# single_asic_miner.net
KiCad netlist of a schematic drawn in EAGLE
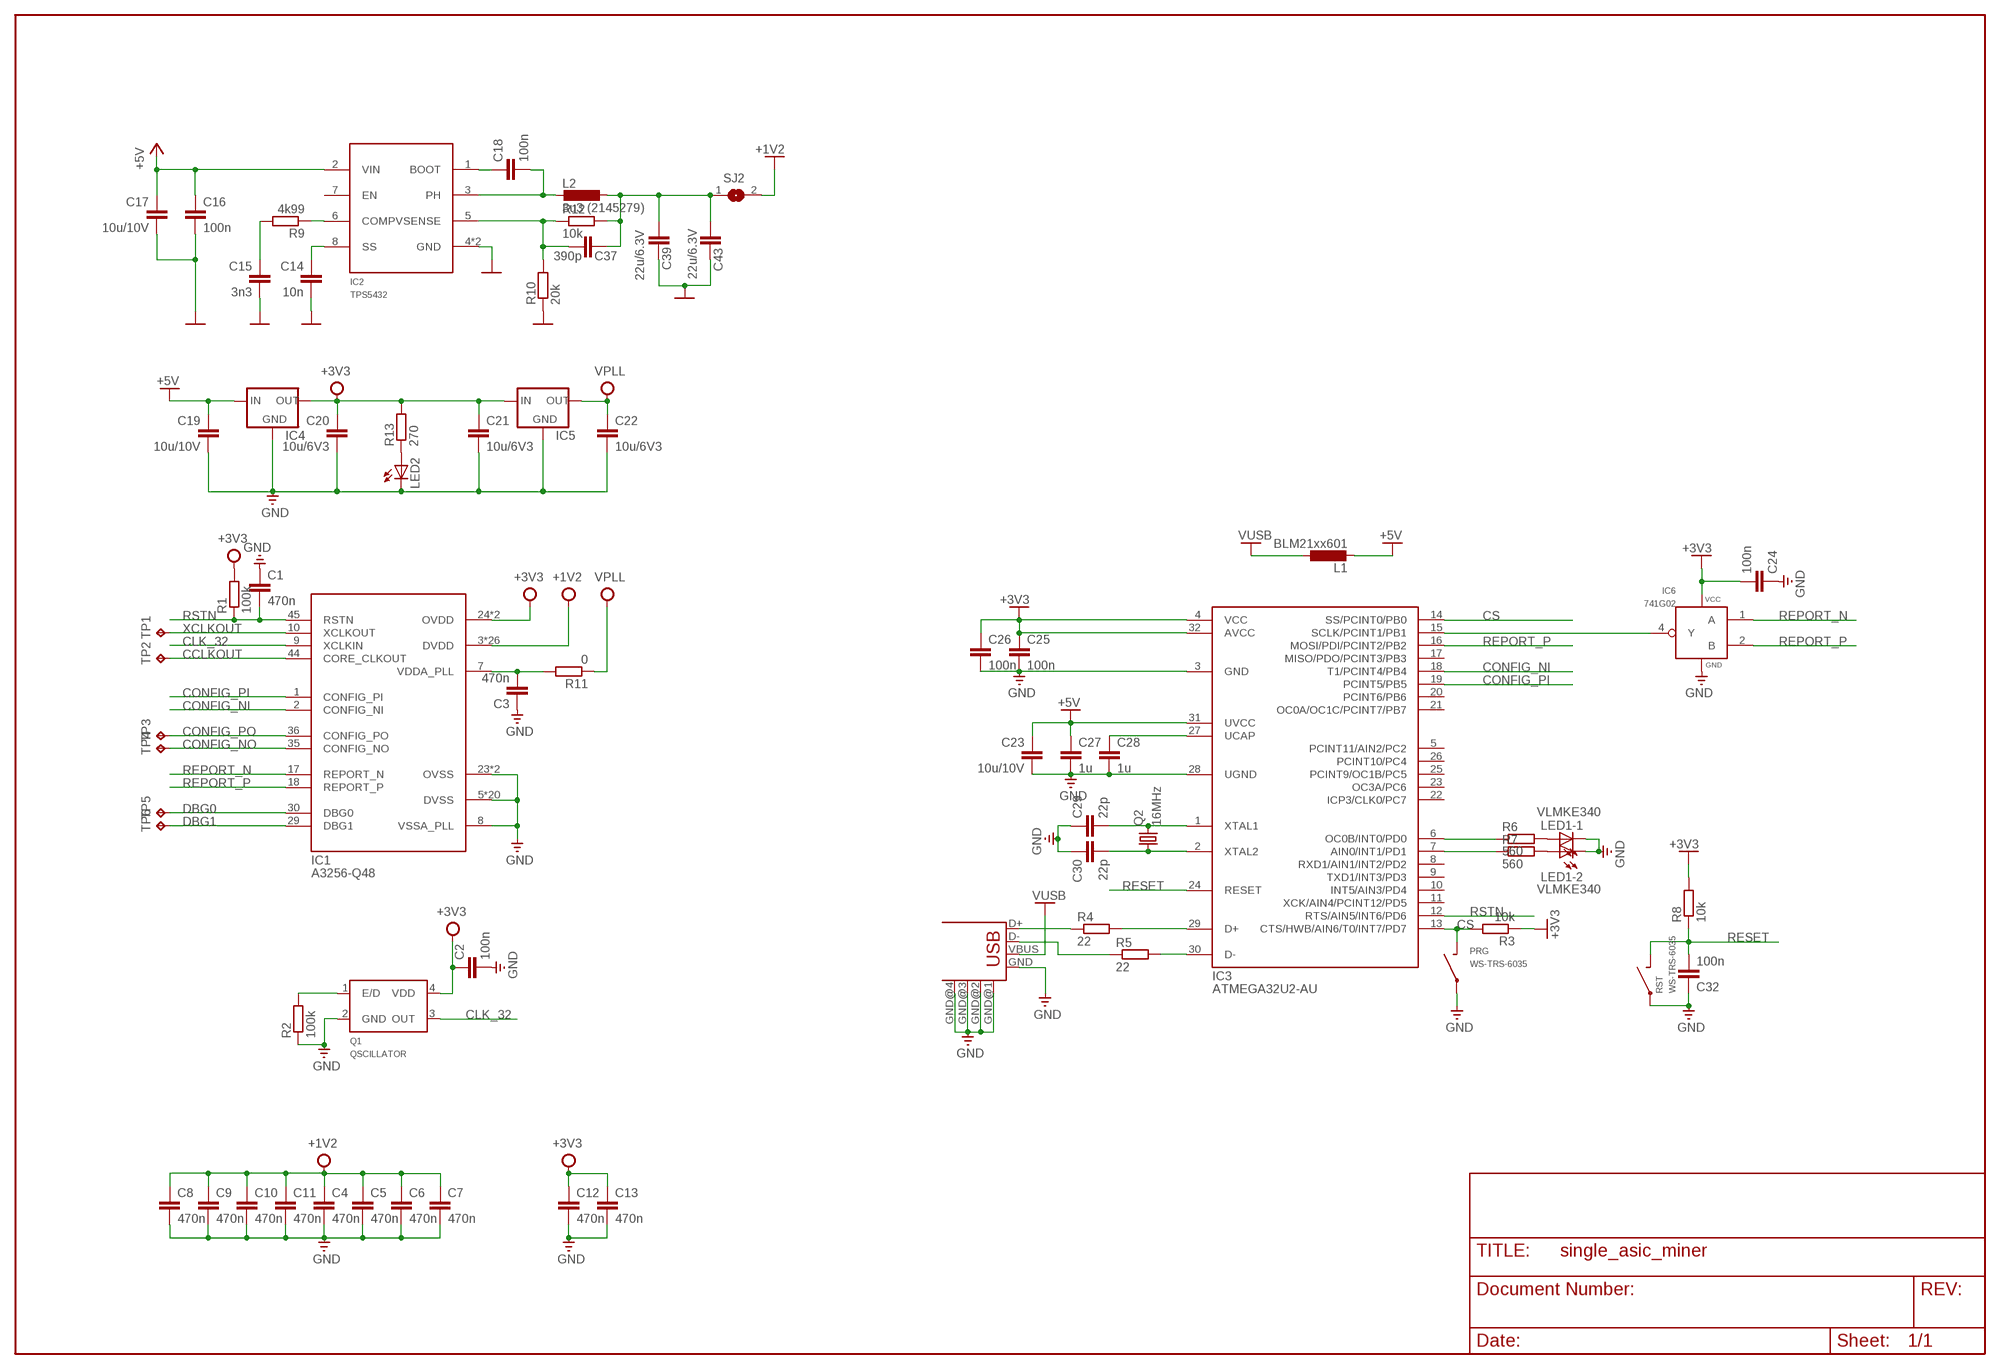
[diagram p0: schematic, sheet 1]

(export (version "E")
  (design (tool "Eeschema 10.0.6"))
  (components
    (comp (ref "C1")
      (value "470n")
      (footprint "eagle-import:C0805")
      (libsource (lib "eagle-import") (part "C-EUC0805"))
    )
    (comp (ref "C2")
      (value "100n")
      (footprint "eagle-import:C0805")
      (libsource (lib "eagle-import") (part "C-EUC0805"))
    )
    (comp (ref "C3")
      (value "470n")
      (footprint "eagle-import:C0805")
      (libsource (lib "eagle-import") (part "C-EUC0805"))
    )
    (comp (ref "C4")
      (value "470n")
      (footprint "eagle-import:C0805")
      (libsource (lib "eagle-import") (part "C-EUC0805"))
    )
    (comp (ref "C5")
      (value "470n")
      (footprint "eagle-import:C0805")
      (libsource (lib "eagle-import") (part "C-EUC0805"))
    )
    (comp (ref "C6")
      (value "470n")
      (footprint "eagle-import:C0805")
      (libsource (lib "eagle-import") (part "C-EUC0805"))
    )
    (comp (ref "C7")
      (value "470n")
      (footprint "eagle-import:C0805")
      (libsource (lib "eagle-import") (part "C-EUC0805"))
    )
    (comp (ref "C8")
      (value "470n")
      (footprint "eagle-import:C0805")
      (libsource (lib "eagle-import") (part "C-EUC0805"))
    )
    (comp (ref "C9")
      (value "470n")
      (footprint "eagle-import:C0805")
      (libsource (lib "eagle-import") (part "C-EUC0805"))
    )
    (comp (ref "C10")
      (value "470n")
      (footprint "eagle-import:C0805")
      (libsource (lib "eagle-import") (part "C-EUC0805"))
    )
    (comp (ref "C11")
      (value "470n")
      (footprint "eagle-import:C0805")
      (libsource (lib "eagle-import") (part "C-EUC0805"))
    )
    (comp (ref "C12")
      (value "470n")
      (footprint "eagle-import:C0805")
      (libsource (lib "eagle-import") (part "C-EUC0805"))
    )
    (comp (ref "C13")
      (value "470n")
      (footprint "eagle-import:C0805")
      (libsource (lib "eagle-import") (part "C-EUC0805"))
    )
    (comp (ref "C14")
      (value "10n")
      (footprint "eagle-import:C0805")
      (libsource (lib "eagle-import") (part "C-EUC0805"))
    )
    (comp (ref "C15")
      (value "3n3")
      (footprint "eagle-import:C0805")
      (libsource (lib "eagle-import") (part "C-EUC0805"))
    )
    (comp (ref "C16")
      (value "100n")
      (footprint "eagle-import:C0805")
      (libsource (lib "eagle-import") (part "C-EUC0805"))
    )
    (comp (ref "C17")
      (value "10u/10V")
      (footprint "eagle-import:C0805")
      (libsource (lib "eagle-import") (part "C-EUC0805"))
    )
    (comp (ref "C18")
      (value "100n")
      (footprint "eagle-import:C0805")
      (libsource (lib "eagle-import") (part "C-EUC0805"))
    )
    (comp (ref "C19")
      (value "10u/10V")
      (footprint "eagle-import:C0805")
      (libsource (lib "eagle-import") (part "C-EUC0805"))
    )
    (comp (ref "C20")
      (value "10u/6V3")
      (footprint "eagle-import:C0805")
      (libsource (lib "eagle-import") (part "C-EUC0805"))
    )
    (comp (ref "C21")
      (value "10u/6V3")
      (footprint "eagle-import:C0805")
      (libsource (lib "eagle-import") (part "C-EUC0805"))
    )
    (comp (ref "C22")
      (value "10u/6V3")
      (footprint "eagle-import:C0805")
      (libsource (lib "eagle-import") (part "C-EUC0805"))
    )
    (comp (ref "C23")
      (value "10u/10V")
      (footprint "eagle-import:C0805")
      (libsource (lib "eagle-import") (part "C-EUC0805"))
    )
    (comp (ref "C24")
      (value "100n")
      (footprint "eagle-import:C0805")
      (libsource (lib "eagle-import") (part "C-EUC0805"))
    )
    (comp (ref "C25")
      (value "100n")
      (footprint "eagle-import:C0805")
      (libsource (lib "eagle-import") (part "C-EUC0805"))
    )
    (comp (ref "C26")
      (value "100n")
      (footprint "eagle-import:C0805")
      (libsource (lib "eagle-import") (part "C-EUC0805"))
    )
    (comp (ref "C27")
      (value "1u")
      (footprint "eagle-import:C0805")
      (libsource (lib "eagle-import") (part "C-EUC0805"))
    )
    (comp (ref "C28")
      (value "1u")
      (footprint "eagle-import:C0805")
      (libsource (lib "eagle-import") (part "C-EUC0805"))
    )
    (comp (ref "C29")
      (value "22p")
      (footprint "eagle-import:C0805")
      (libsource (lib "eagle-import") (part "C-EUC0805"))
    )
    (comp (ref "C30")
      (value "22p")
      (footprint "eagle-import:C0805")
      (libsource (lib "eagle-import") (part "C-EUC0805"))
    )
    (comp (ref "C32")
      (value "100n")
      (footprint "eagle-import:C0805")
      (libsource (lib "eagle-import") (part "C-EUC0805"))
    )
    (comp (ref "C37")
      (value "390p")
      (footprint "eagle-import:C0805")
      (libsource (lib "eagle-import") (part "C-EUC0805"))
    )
    (comp (ref "C39")
      (value "22u/6.3V")
      (footprint "eagle-import:C0805")
      (libsource (lib "eagle-import") (part "C-EUC0805"))
    )
    (comp (ref "C43")
      (value "22u/6.3V")
      (footprint "eagle-import:C0805")
      (libsource (lib "eagle-import") (part "C-EUC0805"))
    )
    (comp (ref "IC1")
      (value "A3256-Q48")
      (footprint "eagle-import:QFN48")
      (libsource (lib "eagle-import") (part "A3256-Q48"))
    )
    (comp (ref "IC2")
      (value "TPS5432")
      (footprint "eagle-import:SO08E")
      (libsource (lib "eagle-import") (part "TPS5432"))
    )
    (comp (ref "IC3")
      (value "ATMEGA32U2-AU")
      (footprint "eagle-import:TQFP32")
      (libsource (lib "eagle-import") (part "ATMEGA32U2-AU"))
    )
    (comp (ref "IC4")
      (value "LM1117")
      (footprint "eagle-import:SOT223")
      (libsource (lib "eagle-import") (part "LM1117"))
    )
    (comp (ref "IC5")
      (value "LM1117")
      (footprint "eagle-import:SOT223")
      (libsource (lib "eagle-import") (part "LM1117"))
    )
    (comp (ref "IC6")
      (value "741G02")
      (footprint "eagle-import:SOT23-5")
      (libsource (lib "eagle-import") (part "741G02"))
    )
    (comp (ref "L1")
      (value "BLM21xx601")
      (footprint "eagle-import:L0805")
      (libsource (lib "eagle-import") (part "L-EUL0805"))
    )
    (comp (ref "L2")
      (value "3u3 (2145279)")
      (footprint "eagle-import:L4540")
      (libsource (lib "eagle-import") (part "L-4540"))
    )
    (comp (ref "LED1")
      (value "VLMKE340")
      (footprint "eagle-import:PLCC4")
      (libsource (lib "eagle-import") (part "VLMKE3400"))
    )
    (comp (ref "LED2")
      (value "LEDCHIP-LED0805")
      (footprint "eagle-import:CHIP-LED0805")
      (libsource (lib "eagle-import") (part "LEDCHIP-LED0805"))
    )
    (comp (ref "PRG")
      (value "WS-TRS-6035")
      (footprint "eagle-import:WS-TRS")
      (libsource (lib "eagle-import") (part "WS-TRS-6035"))
    )
    (comp (ref "Q1")
      (value "QSCILLATOR")
      (footprint "eagle-import:SMD7552")
      (libsource (lib "eagle-import") (part "QSCILLATOR"))
    )
    (comp (ref "Q2")
      (value "16MHz")
      (footprint "eagle-import:6035")
      (libsource (lib "eagle-import") (part "CRYSTAL-ABM7"))
    )
    (comp (ref "R1")
      (value "100k")
      (footprint "eagle-import:R0805")
      (libsource (lib "eagle-import") (part "R-EU_R0805"))
    )
    (comp (ref "R2")
      (value "100k")
      (footprint "eagle-import:R0805")
      (libsource (lib "eagle-import") (part "R-EU_R0805"))
    )
    (comp (ref "R3")
      (value "10k")
      (footprint "eagle-import:R0805")
      (libsource (lib "eagle-import") (part "R-EU_R0805"))
    )
    (comp (ref "R4")
      (value "22")
      (footprint "eagle-import:R0805")
      (libsource (lib "eagle-import") (part "R-EU_R0805"))
    )
    (comp (ref "R5")
      (value "22")
      (footprint "eagle-import:R0805")
      (libsource (lib "eagle-import") (part "R-EU_R0805"))
    )
    (comp (ref "R6")
      (value "560")
      (footprint "eagle-import:R0805")
      (libsource (lib "eagle-import") (part "R-EU_R0805"))
    )
    (comp (ref "R7")
      (value "560")
      (footprint "eagle-import:R0805")
      (libsource (lib "eagle-import") (part "R-EU_R0805"))
    )
    (comp (ref "R8")
      (value "10k")
      (footprint "eagle-import:R0805")
      (libsource (lib "eagle-import") (part "R-EU_R0805"))
    )
    (comp (ref "R9")
      (value "4k99")
      (footprint "eagle-import:R0805")
      (libsource (lib "eagle-import") (part "R-EU_R0805"))
    )
    (comp (ref "R10")
      (value "20k")
      (footprint "eagle-import:R0805")
      (libsource (lib "eagle-import") (part "R-EU_R0805"))
    )
    (comp (ref "R11")
      (value "0")
      (footprint "eagle-import:R0805")
      (libsource (lib "eagle-import") (part "R-EU_R0805"))
    )
    (comp (ref "R12")
      (value "10k")
      (footprint "eagle-import:R0805")
      (libsource (lib "eagle-import") (part "R-EU_R0805"))
    )
    (comp (ref "R13")
      (value "270")
      (footprint "eagle-import:R0805")
      (libsource (lib "eagle-import") (part "R-EU_R0805"))
    )
    (comp (ref "RST")
      (value "WS-TRS-6035")
      (footprint "eagle-import:WS-TRS")
      (libsource (lib "eagle-import") (part "WS-TRS-6035"))
    )
    (comp (ref "SJ2") (value "SJ") (footprint "eagle-import:SJ") (libsource (lib "eagle-import") (part "SJ")))
    (comp (ref "TP1")
      (value "TPB1,27")
      (footprint "eagle-import:B1,27")
      (libsource (lib "eagle-import") (part "TPB1,27"))
    )
    (comp (ref "TP2")
      (value "TPB1,27")
      (footprint "eagle-import:B1,27")
      (libsource (lib "eagle-import") (part "TPB1,27"))
    )
    (comp (ref "TP3")
      (value "TPB1,27")
      (footprint "eagle-import:B1,27")
      (libsource (lib "eagle-import") (part "TPB1,27"))
    )
    (comp (ref "TP4")
      (value "TPB1,27")
      (footprint "eagle-import:B1,27")
      (libsource (lib "eagle-import") (part "TPB1,27"))
    )
    (comp (ref "TP5")
      (value "TPB1,27")
      (footprint "eagle-import:B1,27")
      (libsource (lib "eagle-import") (part "TPB1,27"))
    )
    (comp (ref "TP6")
      (value "TPB1,27")
      (footprint "eagle-import:B1,27")
      (libsource (lib "eagle-import") (part "TPB1,27"))
    )
    (comp (ref "X1")
      (value "USB-SHIELD-1")
      (footprint "eagle-import:USB-M-S1_1")
      (libsource (lib "eagle-import") (part "USB-SHIELD-1"))
    )
  )
  (nets
    (net (code "1") (name "+1V2") (class "Default")
      (node (ref "C10") (pin "1") (pinfunction "1_1") (pintype "passive"))
      (node (ref "C11") (pin "1") (pinfunction "1_1") (pintype "passive"))
      (node (ref "C4") (pin "1") (pinfunction "1_1") (pintype "passive"))
      (node (ref "C5") (pin "1") (pinfunction "1_1") (pintype "passive"))
      (node (ref "C6") (pin "1") (pinfunction "1_1") (pintype "passive"))
      (node (ref "C7") (pin "1") (pinfunction "1_1") (pintype "passive"))
      (node (ref "C8") (pin "1") (pinfunction "1_1") (pintype "passive"))
      (node (ref "C9") (pin "1") (pinfunction "1_1") (pintype "passive"))
      (node (ref "IC1") (pin "11") (pinfunction "DVDD_11") (pintype "power_in"))
      (node (ref "IC1") (pin "12") (pinfunction "DVDD_12") (pintype "power_in"))
      (node (ref "IC1") (pin "13") (pinfunction "DVDD_13") (pintype "power_in"))
      (node (ref "IC1") (pin "14") (pinfunction "DVDD_14") (pintype "power_in"))
      (node (ref "IC1") (pin "15") (pinfunction "DVDD_15") (pintype "power_in"))
      (node (ref "IC1") (pin "16") (pinfunction "DVDD_16") (pintype "power_in"))
      (node (ref "IC1") (pin "19") (pinfunction "DVDD_19") (pintype "power_in"))
      (node (ref "IC1") (pin "21") (pinfunction "DVDD_21") (pintype "power_in"))
      (node (ref "IC1") (pin "22") (pinfunction "DVDD_22") (pintype "power_in"))
      (node (ref "IC1") (pin "25") (pinfunction "DVDD_25") (pintype "power_in"))
      (node (ref "IC1") (pin "26") (pinfunction "DVDD_26") (pintype "power_in"))
      (node (ref "IC1") (pin "27") (pinfunction "DVDD_27") (pintype "power_in"))
      (node (ref "IC1") (pin "28") (pinfunction "DVDD_28") (pintype "power_in"))
      (node (ref "IC1") (pin "3") (pinfunction "DVDD_3") (pintype "power_in"))
      (node (ref "IC1") (pin "31") (pinfunction "DVDD_31") (pintype "power_in"))
      (node (ref "IC1") (pin "33") (pinfunction "DVDD_33") (pintype "power_in"))
      (node (ref "IC1") (pin "34") (pinfunction "DVDD_34") (pintype "power_in"))
      (node (ref "IC1") (pin "39") (pinfunction "DVDD_39") (pintype "power_in"))
      (node (ref "IC1") (pin "4") (pinfunction "DVDD_4") (pintype "power_in"))
      (node (ref "IC1") (pin "40") (pinfunction "DVDD_40") (pintype "power_in"))
      (node (ref "IC1") (pin "41") (pinfunction "DVDD_41") (pintype "power_in"))
      (node (ref "IC1") (pin "43") (pinfunction "DVDD_43") (pintype "power_in"))
      (node (ref "IC1") (pin "46") (pinfunction "DVDD_46") (pintype "power_in"))
      (node (ref "IC1") (pin "47") (pinfunction "DVDD_47") (pintype "power_in"))
      (node (ref "IC1") (pin "48") (pinfunction "DVDD_48") (pintype "power_in"))
      (node (ref "IC1") (pin "6") (pinfunction "DVDD_6") (pintype "power_in"))
      (node (ref "SJ2") (pin "2") (pinfunction "2_2") (pintype "passive"))
    )
    (net (code "2") (name "+3V3") (class "Default")
      (node (ref "C12") (pin "1") (pinfunction "1_1") (pintype "passive"))
      (node (ref "C13") (pin "1") (pinfunction "1_1") (pintype "passive"))
      (node (ref "C2") (pin "1") (pinfunction "1_1") (pintype "passive"))
      (node (ref "C20") (pin "1") (pinfunction "1_1") (pintype "passive"))
      (node (ref "C21") (pin "1") (pinfunction "1_1") (pintype "passive"))
      (node (ref "C24") (pin "2") (pinfunction "2_2") (pintype "passive"))
      (node (ref "C25") (pin "1") (pinfunction "1_1") (pintype "passive"))
      (node (ref "C26") (pin "1") (pinfunction "1_1") (pintype "passive"))
      (node (ref "IC1") (pin "24") (pinfunction "OVDD_24") (pintype "power_in"))
      (node (ref "IC1") (pin "37") (pinfunction "OVDD_37") (pintype "power_in"))
      (node (ref "IC3") (pin "32") (pinfunction "AVCC_32") (pintype "power_in"))
      (node (ref "IC3") (pin "4") (pinfunction "VCC_4") (pintype "power_in"))
      (node (ref "IC4") (pin "2") (pinfunction "OUT_2") (pintype "passive"))
      (node (ref "IC5") (pin "3") (pinfunction "IN_3") (pintype "input"))
      (node (ref "IC6") (pin "5") (pinfunction "VCC_5") (pintype "power_in"))
      (node (ref "Q1") (pin "4") (pinfunction "VDD_4") (pintype "power_in"))
      (node (ref "R1") (pin "2") (pinfunction "2_2") (pintype "passive"))
      (node (ref "R13") (pin "2") (pinfunction "2_2") (pintype "passive"))
      (node (ref "R3") (pin "1") (pinfunction "1_1") (pintype "passive"))
      (node (ref "R8") (pin "2") (pinfunction "2_2") (pintype "passive"))
    )
    (net (code "3") (name "+5V") (class "Default")
      (node (ref "C16") (pin "1") (pinfunction "1_1") (pintype "passive"))
      (node (ref "C17") (pin "1") (pinfunction "1_1") (pintype "passive"))
      (node (ref "C19") (pin "1") (pinfunction "1_1") (pintype "passive"))
      (node (ref "C23") (pin "1") (pinfunction "1_1") (pintype "passive"))
      (node (ref "C27") (pin "1") (pinfunction "1_1") (pintype "passive"))
      (node (ref "IC2") (pin "2") (pinfunction "VIN_2") (pintype "input"))
      (node (ref "IC3") (pin "31") (pinfunction "UVCC_31") (pintype "power_in"))
      (node (ref "IC4") (pin "3") (pinfunction "IN_3") (pintype "input"))
      (node (ref "L1") (pin "2") (pinfunction "2_2") (pintype "passive"))
    )
    (net (code "4") (name "/CCLKOUT") (class "Default")
      (node (ref "IC1") (pin "44") (pinfunction "CORE_CLKOUT_44") (pintype "output"))
      (node (ref "TP2") (pin "TP") (pinfunction "TP_TP") (pintype "input"))
    )
    (net (code "5") (name "/CLK_32") (class "Default")
      (node (ref "IC1") (pin "9") (pinfunction "XCLKIN_9") (pintype "input"))
      (node (ref "Q1") (pin "3") (pinfunction "OUT_3") (pintype "output"))
    )
    (net (code "6") (name "/CONFIG_NI") (class "Default")
      (node (ref "IC1") (pin "2") (pinfunction "CONFIG_NI_2") (pintype "input"))
      (node (ref "IC3") (pin "18") (pinfunction "T1/PCINT4/PB4_18") (pintype "bidirectional"))
    )
    (net (code "7") (name "/CONFIG_NO") (class "Default")
      (node (ref "IC1") (pin "35") (pinfunction "CONFIG_NO_35") (pintype "output"))
      (node (ref "TP4") (pin "TP") (pinfunction "TP_TP") (pintype "input"))
    )
    (net (code "8") (name "/CONFIG_PI") (class "Default")
      (node (ref "IC1") (pin "1") (pinfunction "CONFIG_PI_1") (pintype "input"))
      (node (ref "IC3") (pin "19") (pinfunction "PCINT5/PB5_19") (pintype "bidirectional"))
    )
    (net (code "9") (name "/CONFIG_PO") (class "Default")
      (node (ref "IC1") (pin "36") (pinfunction "CONFIG_PO_36") (pintype "output"))
      (node (ref "TP3") (pin "TP") (pinfunction "TP_TP") (pintype "input"))
    )
    (net (code "10") (name "/CS") (class "Default")
      (node (ref "IC3") (pin "13") (pinfunction "CTS/HWB/AIN6/T0/INT7/PD7_13") (pintype "bidirectional"))
      (node (ref "IC3") (pin "14") (pinfunction "SS/PCINT0/PB0_14") (pintype "bidirectional"))
      (node (ref "PRG") (pin "P$2") (pinfunction "P$2_P$2") (pintype "bidirectional"))
      (node (ref "R3") (pin "2") (pinfunction "2_2") (pintype "passive"))
    )
    (net (code "11") (name "/DBG0") (class "Default")
      (node (ref "IC1") (pin "30") (pinfunction "DBG0_30") (pintype "output"))
      (node (ref "TP5") (pin "TP") (pinfunction "TP_TP") (pintype "input"))
    )
    (net (code "12") (name "/DBG1") (class "Default")
      (node (ref "IC1") (pin "29") (pinfunction "DBG1_29") (pintype "output"))
      (node (ref "TP6") (pin "TP") (pinfunction "TP_TP") (pintype "input"))
    )
    (net (code "13") (name "/REPORT_N") (class "Default")
      (node (ref "IC1") (pin "17") (pinfunction "REPORT_N_17") (pintype "output"))
      (node (ref "IC6") (pin "1") (pinfunction "A_1") (pintype "input"))
    )
    (net (code "14") (name "/REPORT_P") (class "Default")
      (node (ref "IC1") (pin "18") (pinfunction "REPORT_P_18") (pintype "output"))
      (node (ref "IC3") (pin "16") (pinfunction "MOSI/PDI/PCINT2/PB2_16") (pintype "bidirectional"))
      (node (ref "IC6") (pin "2") (pinfunction "B_2") (pintype "input"))
    )
    (net (code "15") (name "/RESET") (class "Default")
      (node (ref "C32") (pin "2") (pinfunction "2_2") (pintype "passive"))
      (node (ref "IC3") (pin "24") (pinfunction "RESET_24") (pintype "input"))
      (node (ref "R8") (pin "1") (pinfunction "1_1") (pintype "passive"))
      (node (ref "RST") (pin "P$2") (pinfunction "P$2_P$2") (pintype "bidirectional"))
    )
    (net (code "16") (name "/RSTN") (class "Default")
      (node (ref "C1") (pin "2") (pinfunction "2_2") (pintype "passive"))
      (node (ref "IC1") (pin "45") (pinfunction "RSTN_45") (pintype "input"))
      (node (ref "IC3") (pin "12") (pinfunction "RTS/AIN5/INT6/PD6_12") (pintype "bidirectional"))
      (node (ref "R1") (pin "1") (pinfunction "1_1") (pintype "passive"))
    )
    (net (code "17") (name "/XCLKOUT") (class "Default")
      (node (ref "IC1") (pin "10") (pinfunction "XCLKOUT_10") (pintype "output"))
      (node (ref "TP1") (pin "TP") (pinfunction "TP_TP") (pintype "input"))
    )
    (net (code "18") (name "GND") (class "Default")
      (node (ref "C1") (pin "1") (pinfunction "1_1") (pintype "passive"))
      (node (ref "C10") (pin "2") (pinfunction "2_2") (pintype "passive"))
      (node (ref "C11") (pin "2") (pinfunction "2_2") (pintype "passive"))
      (node (ref "C12") (pin "2") (pinfunction "2_2") (pintype "passive"))
      (node (ref "C13") (pin "2") (pinfunction "2_2") (pintype "passive"))
      (node (ref "C14") (pin "2") (pinfunction "2_2") (pintype "passive"))
      (node (ref "C15") (pin "2") (pinfunction "2_2") (pintype "passive"))
      (node (ref "C16") (pin "2") (pinfunction "2_2") (pintype "passive"))
      (node (ref "C17") (pin "2") (pinfunction "2_2") (pintype "passive"))
      (node (ref "C19") (pin "2") (pinfunction "2_2") (pintype "passive"))
      (node (ref "C2") (pin "2") (pinfunction "2_2") (pintype "passive"))
      (node (ref "C20") (pin "2") (pinfunction "2_2") (pintype "passive"))
      (node (ref "C21") (pin "2") (pinfunction "2_2") (pintype "passive"))
      (node (ref "C22") (pin "2") (pinfunction "2_2") (pintype "passive"))
      (node (ref "C23") (pin "2") (pinfunction "2_2") (pintype "passive"))
      (node (ref "C24") (pin "1") (pinfunction "1_1") (pintype "passive"))
      (node (ref "C25") (pin "2") (pinfunction "2_2") (pintype "passive"))
      (node (ref "C26") (pin "2") (pinfunction "2_2") (pintype "passive"))
      (node (ref "C27") (pin "2") (pinfunction "2_2") (pintype "passive"))
      (node (ref "C28") (pin "2") (pinfunction "2_2") (pintype "passive"))
      (node (ref "C29") (pin "1") (pinfunction "1_1") (pintype "passive"))
      (node (ref "C3") (pin "1") (pinfunction "1_1") (pintype "passive"))
      (node (ref "C30") (pin "1") (pinfunction "1_1") (pintype "passive"))
      (node (ref "C32") (pin "1") (pinfunction "1_1") (pintype "passive"))
      (node (ref "C39") (pin "2") (pinfunction "2_2") (pintype "passive"))
      (node (ref "C4") (pin "2") (pinfunction "2_2") (pintype "passive"))
      (node (ref "C43") (pin "2") (pinfunction "2_2") (pintype "passive"))
      (node (ref "C5") (pin "2") (pinfunction "2_2") (pintype "passive"))
      (node (ref "C6") (pin "2") (pinfunction "2_2") (pintype "passive"))
      (node (ref "C7") (pin "2") (pinfunction "2_2") (pintype "passive"))
      (node (ref "C8") (pin "2") (pinfunction "2_2") (pintype "passive"))
      (node (ref "C9") (pin "2") (pinfunction "2_2") (pintype "passive"))
      (node (ref "IC1") (pin "20") (pinfunction "DVSS_20") (pintype "power_in"))
      (node (ref "IC1") (pin "23") (pinfunction "OVSS_23") (pintype "power_in"))
      (node (ref "IC1") (pin "32") (pinfunction "DVSS_32") (pintype "power_in"))
      (node (ref "IC1") (pin "38") (pinfunction "OVSS_38") (pintype "power_in"))
      (node (ref "IC1") (pin "42") (pinfunction "DVSS_42") (pintype "power_in"))
      (node (ref "IC1") (pin "5") (pinfunction "DVSS_5") (pintype "power_in"))
      (node (ref "IC1") (pin "8") (pinfunction "VSSA_PLL_8") (pintype "power_in"))
      (node (ref "IC1") (pin "P$1") (pinfunction "DVSS_P$1") (pintype "power_in"))
      (node (ref "IC1") (pin "P$10") (pinfunction "DVSS_P$10") (pintype "power_in"))
      (node (ref "IC1") (pin "P$11") (pinfunction "DVSS_P$11") (pintype "power_in"))
      (node (ref "IC1") (pin "P$12") (pinfunction "DVSS_P$12") (pintype "power_in"))
      (node (ref "IC1") (pin "P$13") (pinfunction "DVSS_P$13") (pintype "power_in"))
      (node (ref "IC1") (pin "P$14") (pinfunction "DVSS_P$14") (pintype "power_in"))
      (node (ref "IC1") (pin "P$15") (pinfunction "DVSS_P$15") (pintype "power_in"))
      (node (ref "IC1") (pin "P$16") (pinfunction "DVSS_P$16") (pintype "power_in"))
      (node (ref "IC1") (pin "P$2") (pinfunction "DVSS_P$2") (pintype "power_in"))
      (node (ref "IC1") (pin "P$3") (pinfunction "DVSS_P$3") (pintype "power_in"))
      (node (ref "IC1") (pin "P$4") (pinfunction "DVSS_P$4") (pintype "power_in"))
      (node (ref "IC1") (pin "P$5") (pinfunction "DVSS_P$5") (pintype "power_in"))
      (node (ref "IC1") (pin "P$6") (pinfunction "DVSS_P$6") (pintype "power_in"))
      (node (ref "IC1") (pin "P$7") (pinfunction "DVSS_P$7") (pintype "power_in"))
      (node (ref "IC1") (pin "P$8") (pinfunction "DVSS_P$8") (pintype "power_in"))
      (node (ref "IC1") (pin "P$9") (pinfunction "DVSS_P$9") (pintype "power_in"))
      (node (ref "IC2") (pin "4") (pinfunction "GND_4") (pintype "power_in"))
      (node (ref "IC2") (pin "E") (pinfunction "GND_E") (pintype "power_in"))
      (node (ref "IC3") (pin "28") (pinfunction "UGND_28") (pintype "power_in"))
      (node (ref "IC3") (pin "3") (pinfunction "GND_3") (pintype "power_in"))
      (node (ref "IC4") (pin "1") (pinfunction "GND_1") (pintype "input"))
      (node (ref "IC5") (pin "1") (pinfunction "GND_1") (pintype "input"))
      (node (ref "IC6") (pin "3") (pinfunction "GND_3") (pintype "power_in"))
      (node (ref "LED1") (pin "C1") (pinfunction "C_C1") (pintype "passive"))
      (node (ref "LED1") (pin "C2") (pinfunction "C_C2") (pintype "passive"))
      (node (ref "LED2") (pin "C") (pinfunction "C_C") (pintype "passive"))
      (node (ref "PRG") (pin "P$1") (pinfunction "P$1_P$1") (pintype "bidirectional"))
      (node (ref "Q1") (pin "2") (pinfunction "GND_2") (pintype "power_in"))
      (node (ref "R10") (pin "1") (pinfunction "1_1") (pintype "passive"))
      (node (ref "R2") (pin "1") (pinfunction "1_1") (pintype "passive"))
      (node (ref "RST") (pin "P$1") (pinfunction "P$1_P$1") (pintype "bidirectional"))
      (node (ref "X1") (pin "GND") (pinfunction "GND_GND") (pintype "bidirectional"))
      (node (ref "X1") (pin "GND@1") (pinfunction "GND_GND@1") (pintype "bidirectional"))
      (node (ref "X1") (pin "GND@2") (pinfunction "GND_GND@2") (pintype "bidirectional"))
      (node (ref "X1") (pin "GND@3") (pinfunction "GND_GND@3") (pintype "bidirectional"))
      (node (ref "X1") (pin "GND@4") (pinfunction "GND_GND@4") (pintype "bidirectional"))
    )
    (net (code "19") (name "Net-(C15-Pad1)") (class "Default")
      (node (ref "C15") (pin "1") (pinfunction "1_1") (pintype "passive"))
      (node (ref "R9") (pin "2") (pinfunction "2_2") (pintype "passive"))
    )
    (net (code "20") (name "Net-(IC1-VDDA_PLL)") (class "Default")
      (node (ref "C3") (pin "2") (pinfunction "2_2") (pintype "passive"))
      (node (ref "IC1") (pin "7") (pinfunction "VDDA_PLL_7") (pintype "power_in"))
      (node (ref "R11") (pin "2") (pinfunction "2_2") (pintype "passive"))
    )
    (net (code "21") (name "Net-(IC2-BOOT)") (class "Default")
      (node (ref "C18") (pin "1") (pinfunction "1_1") (pintype "passive"))
      (node (ref "IC2") (pin "1") (pinfunction "BOOT_1") (pintype "passive"))
    )
    (net (code "22") (name "Net-(IC2-COMP)") (class "Default")
      (node (ref "IC2") (pin "6") (pinfunction "COMP_6") (pintype "output"))
      (node (ref "R9") (pin "1") (pinfunction "1_1") (pintype "passive"))
    )
    (net (code "23") (name "Net-(IC2-PH)") (class "Default")
      (node (ref "C18") (pin "2") (pinfunction "2_2") (pintype "passive"))
      (node (ref "IC2") (pin "3") (pinfunction "PH_3") (pintype "output"))
      (node (ref "L2") (pin "P$2") (pinfunction "2_P$2") (pintype "passive"))
    )
    (net (code "24") (name "Net-(IC2-SS)") (class "Default")
      (node (ref "C14") (pin "1") (pinfunction "1_1") (pintype "passive"))
      (node (ref "IC2") (pin "8") (pinfunction "SS_8") (pintype "output"))
    )
    (net (code "25") (name "Net-(IC2-VSENSE)") (class "Default")
      (node (ref "C37") (pin "2") (pinfunction "2_2") (pintype "passive"))
      (node (ref "IC2") (pin "5") (pinfunction "VSENSE_5") (pintype "input"))
      (node (ref "R10") (pin "2") (pinfunction "2_2") (pintype "passive"))
      (node (ref "R12") (pin "1") (pinfunction "1_1") (pintype "passive"))
    )
    (net (code "26") (name "Net-(IC3-AIN0{slash}INT1{slash}PD1)") (class "Default")
      (node (ref "IC3") (pin "7") (pinfunction "AIN0/INT1/PD1_7") (pintype "bidirectional"))
      (node (ref "R7") (pin "1") (pinfunction "1_1") (pintype "passive"))
    )
    (net (code "27") (name "Net-(IC3-D+)") (class "Default")
      (node (ref "IC3") (pin "29") (pinfunction "D+_29") (pintype "bidirectional"))
      (node (ref "R4") (pin "2") (pinfunction "2_2") (pintype "passive"))
    )
    (net (code "28") (name "Net-(IC3-D-)") (class "Default")
      (node (ref "IC3") (pin "30") (pinfunction "D-_30") (pintype "bidirectional"))
      (node (ref "R5") (pin "2") (pinfunction "2_2") (pintype "passive"))
    )
    (net (code "29") (name "Net-(IC3-OC0B{slash}INT0{slash}PD0)") (class "Default")
      (node (ref "IC3") (pin "6") (pinfunction "OC0B/INT0/PD0_6") (pintype "bidirectional"))
      (node (ref "R6") (pin "1") (pinfunction "1_1") (pintype "passive"))
    )
    (net (code "30") (name "Net-(IC3-SCLK{slash}PCINT1{slash}PB1)") (class "Default")
      (node (ref "IC3") (pin "15") (pinfunction "SCLK/PCINT1/PB1_15") (pintype "bidirectional"))
      (node (ref "IC6") (pin "4") (pinfunction "Y_4") (pintype "output"))
    )
    (net (code "31") (name "Net-(IC3-UCAP)") (class "Default")
      (node (ref "C28") (pin "1") (pinfunction "1_1") (pintype "passive"))
      (node (ref "IC3") (pin "27") (pinfunction "UCAP_27") (pintype "passive"))
    )
    (net (code "32") (name "Net-(IC3-XTAL1)") (class "Default")
      (node (ref "C29") (pin "2") (pinfunction "2_2") (pintype "passive"))
      (node (ref "IC3") (pin "1") (pinfunction "XTAL1_1") (pintype "passive"))
      (node (ref "Q2") (pin "P$2") (pinfunction "2_P$2") (pintype "passive"))
    )
    (net (code "33") (name "Net-(IC3-XTAL2)") (class "Default")
      (node (ref "C30") (pin "2") (pinfunction "2_2") (pintype "passive"))
      (node (ref "IC3") (pin "2") (pinfunction "XTAL2_2") (pintype "passive"))
      (node (ref "Q2") (pin "P$1") (pinfunction "1_P$1") (pintype "passive"))
    )
    (net (code "34") (name "Net-(L2-1)") (class "Default")
      (node (ref "C37") (pin "1") (pinfunction "1_1") (pintype "passive"))
      (node (ref "C39") (pin "1") (pinfunction "1_1") (pintype "passive"))
      (node (ref "C43") (pin "1") (pinfunction "1_1") (pintype "passive"))
      (node (ref "L2") (pin "P$1") (pinfunction "1_P$1") (pintype "passive"))
      (node (ref "R12") (pin "2") (pinfunction "2_2") (pintype "passive"))
      (node (ref "SJ2") (pin "1") (pinfunction "1_1") (pintype "passive"))
    )
    (net (code "35") (name "Net-(LED1A-A)") (class "Default")
      (node (ref "LED1") (pin "A1") (pinfunction "A_A1") (pintype "passive"))
      (node (ref "R6") (pin "2") (pinfunction "2_2") (pintype "passive"))
    )
    (net (code "36") (name "Net-(LED1B-A)") (class "Default")
      (node (ref "LED1") (pin "A2") (pinfunction "A_A2") (pintype "passive"))
      (node (ref "R7") (pin "2") (pinfunction "2_2") (pintype "passive"))
    )
    (net (code "37") (name "Net-(LED2-PadA)") (class "Default")
      (node (ref "LED2") (pin "A") (pinfunction "A_A") (pintype "passive"))
      (node (ref "R13") (pin "1") (pinfunction "1_1") (pintype "passive"))
    )
    (net (code "38") (name "Net-(Q1-E{slash}D)") (class "Default")
      (node (ref "Q1") (pin "1") (pinfunction "E/D_1") (pintype "input"))
      (node (ref "R2") (pin "2") (pinfunction "2_2") (pintype "passive"))
    )
    (net (code "39") (name "Net-(R4-Pad1)") (class "Default")
      (node (ref "R4") (pin "1") (pinfunction "1_1") (pintype "passive"))
      (node (ref "X1") (pin "D+") (pinfunction "D+_D+") (pintype "bidirectional"))
    )
    (net (code "40") (name "Net-(R5-Pad1)") (class "Default")
      (node (ref "R5") (pin "1") (pinfunction "1_1") (pintype "passive"))
      (node (ref "X1") (pin "D-") (pinfunction "D-_D-") (pintype "bidirectional"))
    )
    (net (code "41") (name "VPLL") (class "Default")
      (node (ref "C22") (pin "1") (pinfunction "1_1") (pintype "passive"))
      (node (ref "IC5") (pin "2") (pinfunction "OUT_2") (pintype "passive"))
      (node (ref "R11") (pin "1") (pinfunction "1_1") (pintype "passive"))
    )
    (net (code "42") (name "VUSB") (class "Default")
      (node (ref "L1") (pin "1") (pinfunction "1_1") (pintype "passive"))
      (node (ref "X1") (pin "VBUS") (pinfunction "VBUS_VBUS") (pintype "bidirectional"))
    )
    (net (code "43") (name "unconnected-(IC2-EN-Pad7)") (class "Default")
      (node (ref "IC2") (pin "7") (pinfunction "EN_7") (pintype "passive"))
    )
    (net (code "44") (name "unconnected-(IC3-ICP3{slash}CLK0{slash}PC7-Pad22)") (class "Default")
      (node (ref "IC3") (pin "22") (pinfunction "ICP3/CLK0/PC7_22") (pintype "bidirectional"))
    )
    (net (code "45") (name "unconnected-(IC3-INT5{slash}AIN3{slash}PD4-Pad10)") (class "Default")
      (node (ref "IC3") (pin "10") (pinfunction "INT5/AIN3/PD4_10") (pintype "bidirectional"))
    )
    (net (code "46") (name "unconnected-(IC3-MISO{slash}PDO{slash}PCINT3{slash}PB3-Pad17)") (class "Default")
      (node (ref "IC3") (pin "17") (pinfunction "MISO/PDO/PCINT3/PB3_17") (pintype "bidirectional"))
    )
    (net (code "47") (name "unconnected-(IC3-OC0A{slash}OC1C{slash}PCINT7{slash}PB7-Pad21)") (class "Default")
      (node (ref "IC3") (pin "21") (pinfunction "OC0A/OC1C/PCINT7/PB7_21") (pintype "bidirectional"))
    )
    (net (code "48") (name "unconnected-(IC3-OC3A{slash}PC6-Pad23)") (class "Default")
      (node (ref "IC3") (pin "23") (pinfunction "OC3A/PC6_23") (pintype "bidirectional"))
    )
    (net (code "49") (name "unconnected-(IC3-PCINT6{slash}PB6-Pad20)") (class "Default")
      (node (ref "IC3") (pin "20") (pinfunction "PCINT6/PB6_20") (pintype "bidirectional"))
    )
    (net (code "50") (name "unconnected-(IC3-PCINT9{slash}OC1B{slash}PC5-Pad25)") (class "Default")
      (node (ref "IC3") (pin "25") (pinfunction "PCINT9/OC1B/PC5_25") (pintype "bidirectional"))
    )
    (net (code "51") (name "unconnected-(IC3-PCINT10{slash}PC4-Pad26)") (class "Default")
      (node (ref "IC3") (pin "26") (pinfunction "PCINT10/PC4_26") (pintype "bidirectional"))
    )
    (net (code "52") (name "unconnected-(IC3-PCINT11{slash}AIN2{slash}PC2-Pad5)") (class "Default")
      (node (ref "IC3") (pin "5") (pinfunction "PCINT11/AIN2/PC2_5") (pintype "bidirectional"))
    )
    (net (code "53") (name "unconnected-(IC3-RXD1{slash}AIN1{slash}INT2{slash}PD2-Pad8)") (class "Default")
      (node (ref "IC3") (pin "8") (pinfunction "RXD1/AIN1/INT2/PD2_8") (pintype "bidirectional"))
    )
    (net (code "54") (name "unconnected-(IC3-TXD1{slash}INT3{slash}PD3-Pad9)") (class "Default")
      (node (ref "IC3") (pin "9") (pinfunction "TXD1/INT3/PD3_9") (pintype "bidirectional"))
    )
    (net (code "55") (name "unconnected-(IC3-XCK{slash}AIN4{slash}PCINT12{slash}PD5-Pad11)") (class "Default")
      (node (ref "IC3") (pin "11") (pinfunction "XCK/AIN4/PCINT12/PD5_11") (pintype "bidirectional"))
    )
  )
)
